# GPS_Lion.net
KiCad netlist of a schematic drawn in EAGLE
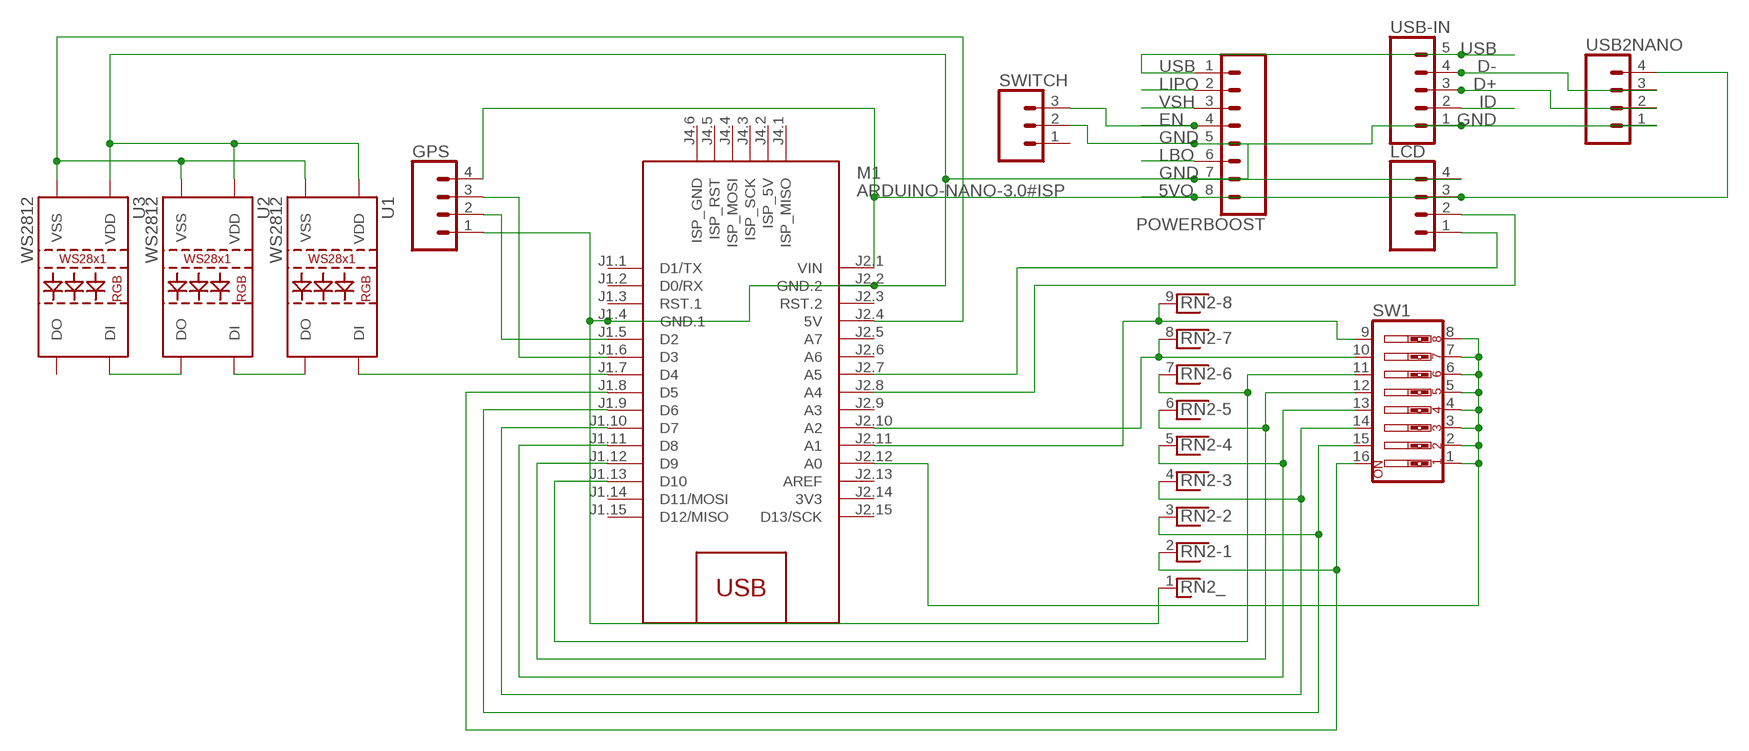
[diagram p0: schematic, sheet 1]

(export (version "E")
  (design (tool "Eeschema 10.0.6"))
  (components
    (comp (ref "GPS")
      (value "CONN_04")
      (footprint "eagle-import:1X04")
      (libsource (lib "eagle-import") (part "CONN_04"))
    )
    (comp (ref "LCD")
      (value "CONN_04")
      (footprint "eagle-import:1X04")
      (libsource (lib "eagle-import") (part "CONN_04"))
    )
    (comp (ref "M1")
      (value "ARDUINO-NANO-3.0#ISP")
      (footprint "eagle-import:ARDUINO-NANO-3.0#ISP")
      (libsource (lib "eagle-import") (part "ARDUINO-NANO-3.0#ISP"))
    )
    (comp (ref "POWERBOOST")
      (value "CONN_08\"")
      (footprint "eagle-import:1X08")
      (libsource (lib "eagle-import") (part "CONN_08{dblquote}"))
    )
    (comp (ref "RN2")
      (value "RNX8")
      (footprint "eagle-import:RN-9")
      (libsource (lib "eagle-import") (part "RNX8"))
    )
    (comp (ref "SW1")
      (value "SW_DIP-8")
      (footprint "eagle-import:EDG-08")
      (libsource (lib "eagle-import") (part "SW_DIP-8"))
    )
    (comp (ref "SWITCH")
      (value "CONN_03")
      (footprint "eagle-import:1X03")
      (libsource (lib "eagle-import") (part "CONN_03"))
    )
    (comp (ref "U1")
      (value "WS2812")
      (footprint "eagle-import:LED-TRICOLOR-5050-IC")
      (libsource (lib "eagle-import") (part "WS2812{dblquote}"))
    )
    (comp (ref "U2")
      (value "WS2812")
      (footprint "eagle-import:LED-TRICOLOR-5050-IC")
      (libsource (lib "eagle-import") (part "WS2812{dblquote}"))
    )
    (comp (ref "U3")
      (value "WS2812")
      (footprint "eagle-import:LED-TRICOLOR-5050-IC")
      (libsource (lib "eagle-import") (part "WS2812{dblquote}"))
    )
    (comp (ref "USB-IN")
      (value "CONN_05")
      (footprint "eagle-import:1X05")
      (libsource (lib "eagle-import") (part "CONN_05"))
    )
    (comp (ref "USB2NANO")
      (value "CONN_04")
      (footprint "eagle-import:1X04")
      (libsource (lib "eagle-import") (part "CONN_04"))
    )
  )
  (nets
    (net (code "1") (name "/3V3") (class "Default")
      (node (ref "M1") (pin "J2.14") (pinfunction "3V3_J2.14") (pintype "power_in"))
    )
    (net (code "2") (name "/5VO") (class "Default")
      (node (ref "GPS") (pin "4") (pinfunction "4_4") (pintype "passive"))
      (node (ref "LCD") (pin "3") (pinfunction "3_3") (pintype "passive"))
      (node (ref "M1") (pin "J2.1") (pinfunction "VIN_J2.1") (pintype "power_in"))
      (node (ref "POWERBOOST") (pin "8") (pinfunction "8_8") (pintype "passive"))
      (node (ref "USB2NANO") (pin "4") (pinfunction "4_4") (pintype "passive"))
    )
    (net (code "3") (name "/D+") (class "Default")
      (node (ref "USB-IN") (pin "3") (pinfunction "3_3") (pintype "passive"))
      (node (ref "USB2NANO") (pin "2") (pinfunction "2_2") (pintype "passive"))
    )
    (net (code "4") (name "/D-") (class "Default")
      (node (ref "USB-IN") (pin "4") (pinfunction "4_4") (pintype "passive"))
      (node (ref "USB2NANO") (pin "3") (pinfunction "3_3") (pintype "passive"))
    )
    (net (code "5") (name "/EN") (class "Default")
      (node (ref "POWERBOOST") (pin "4") (pinfunction "4_4") (pintype "passive"))
      (node (ref "SWITCH") (pin "3") (pinfunction "3_3") (pintype "passive"))
    )
    (net (code "6") (name "/GND") (class "Default")
      (node (ref "GPS") (pin "1") (pinfunction "1_1") (pintype "passive"))
      (node (ref "LCD") (pin "4") (pinfunction "4_4") (pintype "passive"))
      (node (ref "M1") (pin "J1.4") (pinfunction "GND.1_J1.4") (pintype "power_in"))
      (node (ref "M1") (pin "J2.2") (pinfunction "GND.2_J2.2") (pintype "power_in"))
      (node (ref "POWERBOOST") (pin "5") (pinfunction "5_5") (pintype "passive"))
      (node (ref "POWERBOOST") (pin "7") (pinfunction "7_7") (pintype "passive"))
      (node (ref "RN2") (pin "1") (pinfunction "1_1") (pintype "passive"))
      (node (ref "SWITCH") (pin "2") (pinfunction "2_2") (pintype "passive"))
      (node (ref "U1") (pin "3") (pinfunction "VDD_3") (pintype "bidirectional"))
      (node (ref "U1") (pin "5") (pinfunction "VDD_5") (pintype "bidirectional"))
      (node (ref "U2") (pin "3") (pinfunction "VDD_3") (pintype "bidirectional"))
      (node (ref "U2") (pin "5") (pinfunction "VDD_5") (pintype "bidirectional"))
      (node (ref "U3") (pin "3") (pinfunction "VDD_3") (pintype "bidirectional"))
      (node (ref "U3") (pin "5") (pinfunction "VDD_5") (pintype "bidirectional"))
      (node (ref "USB-IN") (pin "1") (pinfunction "1_1") (pintype "passive"))
      (node (ref "USB2NANO") (pin "1") (pinfunction "1_1") (pintype "passive"))
    )
    (net (code "7") (name "/ID") (class "Default")
      (node (ref "USB-IN") (pin "2") (pinfunction "2_2") (pintype "passive"))
    )
    (net (code "8") (name "/LBO") (class "Default")
      (node (ref "POWERBOOST") (pin "6") (pinfunction "6_6") (pintype "passive"))
    )
    (net (code "9") (name "/LIPO") (class "Default")
      (node (ref "POWERBOOST") (pin "2") (pinfunction "2_2") (pintype "passive"))
    )
    (net (code "10") (name "/USB") (class "Default")
      (node (ref "POWERBOOST") (pin "1") (pinfunction "1_1") (pintype "passive"))
      (node (ref "USB-IN") (pin "5") (pinfunction "5_5") (pintype "passive"))
    )
    (net (code "11") (name "/VSH") (class "Default")
      (node (ref "POWERBOOST") (pin "3") (pinfunction "3_3") (pintype "passive"))
    )
    (net (code "12") (name "Net-(M1-5V)") (class "Default")
      (node (ref "M1") (pin "J2.4") (pinfunction "5V_J2.4") (pintype "power_in"))
      (node (ref "U1") (pin "6") (pinfunction "VSS_6") (pintype "bidirectional"))
      (node (ref "U2") (pin "6") (pinfunction "VSS_6") (pintype "bidirectional"))
      (node (ref "U3") (pin "6") (pinfunction "VSS_6") (pintype "bidirectional"))
    )
    (net (code "13") (name "Net-(M1-A0)") (class "Default")
      (node (ref "M1") (pin "J2.12") (pinfunction "A0_J2.12") (pintype "bidirectional"))
      (node (ref "SW1") (pin "1") (pinfunction "1_1") (pintype "passive"))
      (node (ref "SW1") (pin "2") (pinfunction "2_2") (pintype "passive"))
      (node (ref "SW1") (pin "3") (pinfunction "3_3") (pintype "passive"))
      (node (ref "SW1") (pin "4") (pinfunction "4_4") (pintype "passive"))
      (node (ref "SW1") (pin "5") (pinfunction "5_5") (pintype "passive"))
      (node (ref "SW1") (pin "6") (pinfunction "6_6") (pintype "passive"))
      (node (ref "SW1") (pin "7") (pinfunction "7_7") (pintype "passive"))
      (node (ref "SW1") (pin "8") (pinfunction "8_8") (pintype "passive"))
    )
    (net (code "14") (name "Net-(M1-A1)") (class "Default")
      (node (ref "M1") (pin "J2.11") (pinfunction "A1_J2.11") (pintype "bidirectional"))
      (node (ref "RN2") (pin "9") (pinfunction "1_9") (pintype "passive"))
      (node (ref "SW1") (pin "9") (pinfunction "9_9") (pintype "passive"))
    )
    (net (code "15") (name "Net-(M1-A2)") (class "Default")
      (node (ref "M1") (pin "J2.10") (pinfunction "A2_J2.10") (pintype "bidirectional"))
      (node (ref "RN2") (pin "8") (pinfunction "1_8") (pintype "passive"))
      (node (ref "SW1") (pin "10") (pinfunction "10_10") (pintype "passive"))
    )
    (net (code "16") (name "Net-(M1-A4)") (class "Default")
      (node (ref "LCD") (pin "2") (pinfunction "2_2") (pintype "passive"))
      (node (ref "M1") (pin "J2.8") (pinfunction "A4_J2.8") (pintype "bidirectional"))
    )
    (net (code "17") (name "Net-(M1-A5)") (class "Default")
      (node (ref "LCD") (pin "1") (pinfunction "1_1") (pintype "passive"))
      (node (ref "M1") (pin "J2.7") (pinfunction "A5_J2.7") (pintype "bidirectional"))
    )
    (net (code "18") (name "Net-(M1-D2)") (class "Default")
      (node (ref "GPS") (pin "2") (pinfunction "2_2") (pintype "passive"))
      (node (ref "M1") (pin "J1.5") (pinfunction "D2_J1.5") (pintype "bidirectional"))
    )
    (net (code "19") (name "Net-(M1-D3)") (class "Default")
      (node (ref "GPS") (pin "3") (pinfunction "3_3") (pintype "passive"))
      (node (ref "M1") (pin "J1.6") (pinfunction "D3_J1.6") (pintype "bidirectional"))
    )
    (net (code "20") (name "Net-(M1-D4)") (class "Default")
      (node (ref "M1") (pin "J1.7") (pinfunction "D4_J1.7") (pintype "bidirectional"))
      (node (ref "U1") (pin "2") (pinfunction "DI_2") (pintype "bidirectional"))
    )
    (net (code "21") (name "Net-(M1-D5)") (class "Default")
      (node (ref "M1") (pin "J1.8") (pinfunction "D5_J1.8") (pintype "bidirectional"))
      (node (ref "RN2") (pin "2") (pinfunction "1_2") (pintype "passive"))
      (node (ref "SW1") (pin "16") (pinfunction "16_16") (pintype "passive"))
    )
    (net (code "22") (name "Net-(M1-D6)") (class "Default")
      (node (ref "M1") (pin "J1.9") (pinfunction "D6_J1.9") (pintype "bidirectional"))
      (node (ref "RN2") (pin "3") (pinfunction "1_3") (pintype "passive"))
      (node (ref "SW1") (pin "15") (pinfunction "15_15") (pintype "passive"))
    )
    (net (code "23") (name "Net-(M1-D7)") (class "Default")
      (node (ref "M1") (pin "J1.10") (pinfunction "D7_J1.10") (pintype "bidirectional"))
      (node (ref "RN2") (pin "4") (pinfunction "1_4") (pintype "passive"))
      (node (ref "SW1") (pin "14") (pinfunction "14_14") (pintype "passive"))
    )
    (net (code "24") (name "Net-(M1-D8)") (class "Default")
      (node (ref "M1") (pin "J1.11") (pinfunction "D8_J1.11") (pintype "bidirectional"))
      (node (ref "RN2") (pin "5") (pinfunction "1_5") (pintype "passive"))
      (node (ref "SW1") (pin "13") (pinfunction "13_13") (pintype "passive"))
    )
    (net (code "25") (name "Net-(M1-D9)") (class "Default")
      (node (ref "M1") (pin "J1.12") (pinfunction "D9_J1.12") (pintype "bidirectional"))
      (node (ref "RN2") (pin "6") (pinfunction "1_6") (pintype "passive"))
      (node (ref "SW1") (pin "12") (pinfunction "12_12") (pintype "passive"))
    )
    (net (code "26") (name "Net-(M1-D10)") (class "Default")
      (node (ref "M1") (pin "J1.13") (pinfunction "D10_J1.13") (pintype "bidirectional"))
      (node (ref "RN2") (pin "7") (pinfunction "1_7") (pintype "passive"))
      (node (ref "SW1") (pin "11") (pinfunction "11_11") (pintype "passive"))
    )
    (net (code "27") (name "Net-(U1-DO)") (class "Default")
      (node (ref "U1") (pin "1") (pinfunction "DO_1") (pintype "bidirectional"))
      (node (ref "U2") (pin "2") (pinfunction "DI_2") (pintype "bidirectional"))
    )
    (net (code "28") (name "Net-(U2-DO)") (class "Default")
      (node (ref "U2") (pin "1") (pinfunction "DO_1") (pintype "bidirectional"))
      (node (ref "U3") (pin "2") (pinfunction "DI_2") (pintype "bidirectional"))
    )
    (net (code "29") (name "unconnected-(M1-A3-PadJ2.9)") (class "Default")
      (node (ref "M1") (pin "J2.9") (pinfunction "A3_J2.9") (pintype "bidirectional"))
    )
    (net (code "30") (name "unconnected-(M1-A6-PadJ2.6)") (class "Default")
      (node (ref "M1") (pin "J2.6") (pinfunction "A6_J2.6") (pintype "bidirectional"))
    )
    (net (code "31") (name "unconnected-(M1-A7-PadJ2.5)") (class "Default")
      (node (ref "M1") (pin "J2.5") (pinfunction "A7_J2.5") (pintype "bidirectional"))
    )
    (net (code "32") (name "unconnected-(M1-AREF-PadJ2.13)") (class "Default")
      (node (ref "M1") (pin "J2.13") (pinfunction "AREF_J2.13") (pintype "bidirectional"))
    )
    (net (code "33") (name "unconnected-(M1-D0{slash}RX-PadJ1.2)") (class "Default")
      (node (ref "M1") (pin "J1.2") (pinfunction "D0/RX_J1.2") (pintype "bidirectional"))
    )
    (net (code "34") (name "unconnected-(M1-D1{slash}TX-PadJ1.1)") (class "Default")
      (node (ref "M1") (pin "J1.1") (pinfunction "D1/TX_J1.1") (pintype "bidirectional"))
    )
    (net (code "35") (name "unconnected-(M1-D11{slash}MOSI-PadJ1.14)") (class "Default")
      (node (ref "M1") (pin "J1.14") (pinfunction "D11/MOSI_J1.14") (pintype "bidirectional"))
    )
    (net (code "36") (name "unconnected-(M1-D12{slash}MISO-PadJ1.15)") (class "Default")
      (node (ref "M1") (pin "J1.15") (pinfunction "D12/MISO_J1.15") (pintype "bidirectional"))
    )
    (net (code "37") (name "unconnected-(M1-D13{slash}SCK-PadJ2.15)") (class "Default")
      (node (ref "M1") (pin "J2.15") (pinfunction "D13/SCK_J2.15") (pintype "bidirectional"))
    )
    (net (code "38") (name "unconnected-(M1-ISP_5V-PadJ4.2)") (class "Default")
      (node (ref "M1") (pin "J4.2") (pinfunction "ISP_5V_J4.2") (pintype "bidirectional"))
    )
    (net (code "39") (name "unconnected-(M1-ISP_GND-PadJ4.6)") (class "Default")
      (node (ref "M1") (pin "J4.6") (pinfunction "ISP_GND_J4.6") (pintype "bidirectional"))
    )
    (net (code "40") (name "unconnected-(M1-ISP_MISO-PadJ4.1)") (class "Default")
      (node (ref "M1") (pin "J4.1") (pinfunction "ISP_MISO_J4.1") (pintype "bidirectional"))
    )
    (net (code "41") (name "unconnected-(M1-ISP_MOSI-PadJ4.4)") (class "Default")
      (node (ref "M1") (pin "J4.4") (pinfunction "ISP_MOSI_J4.4") (pintype "bidirectional"))
    )
    (net (code "42") (name "unconnected-(M1-ISP_RST-PadJ4.5)") (class "Default")
      (node (ref "M1") (pin "J4.5") (pinfunction "ISP_RST_J4.5") (pintype "bidirectional"))
    )
    (net (code "43") (name "unconnected-(M1-ISP_SCK-PadJ4.3)") (class "Default")
      (node (ref "M1") (pin "J4.3") (pinfunction "ISP_SCK_J4.3") (pintype "bidirectional"))
    )
    (net (code "44") (name "unconnected-(M1-RST.1-PadJ1.3)") (class "Default")
      (node (ref "M1") (pin "J1.3") (pinfunction "RST.1_J1.3") (pintype "bidirectional"))
    )
    (net (code "45") (name "unconnected-(M1-RST.2-PadJ2.3)") (class "Default")
      (node (ref "M1") (pin "J2.3") (pinfunction "RST.2_J2.3") (pintype "bidirectional"))
    )
    (net (code "46") (name "unconnected-(SWITCH-Pad1)") (class "Default")
      (node (ref "SWITCH") (pin "1") (pinfunction "1_1") (pintype "passive"))
    )
    (net (code "47") (name "unconnected-(U3-DO-Pad1)") (class "Default")
      (node (ref "U3") (pin "1") (pinfunction "DO_1") (pintype "bidirectional"))
    )
  )
)
